# CircuitDiagramSheet.net
KiCad netlist of a schematic drawn in EasyEDA
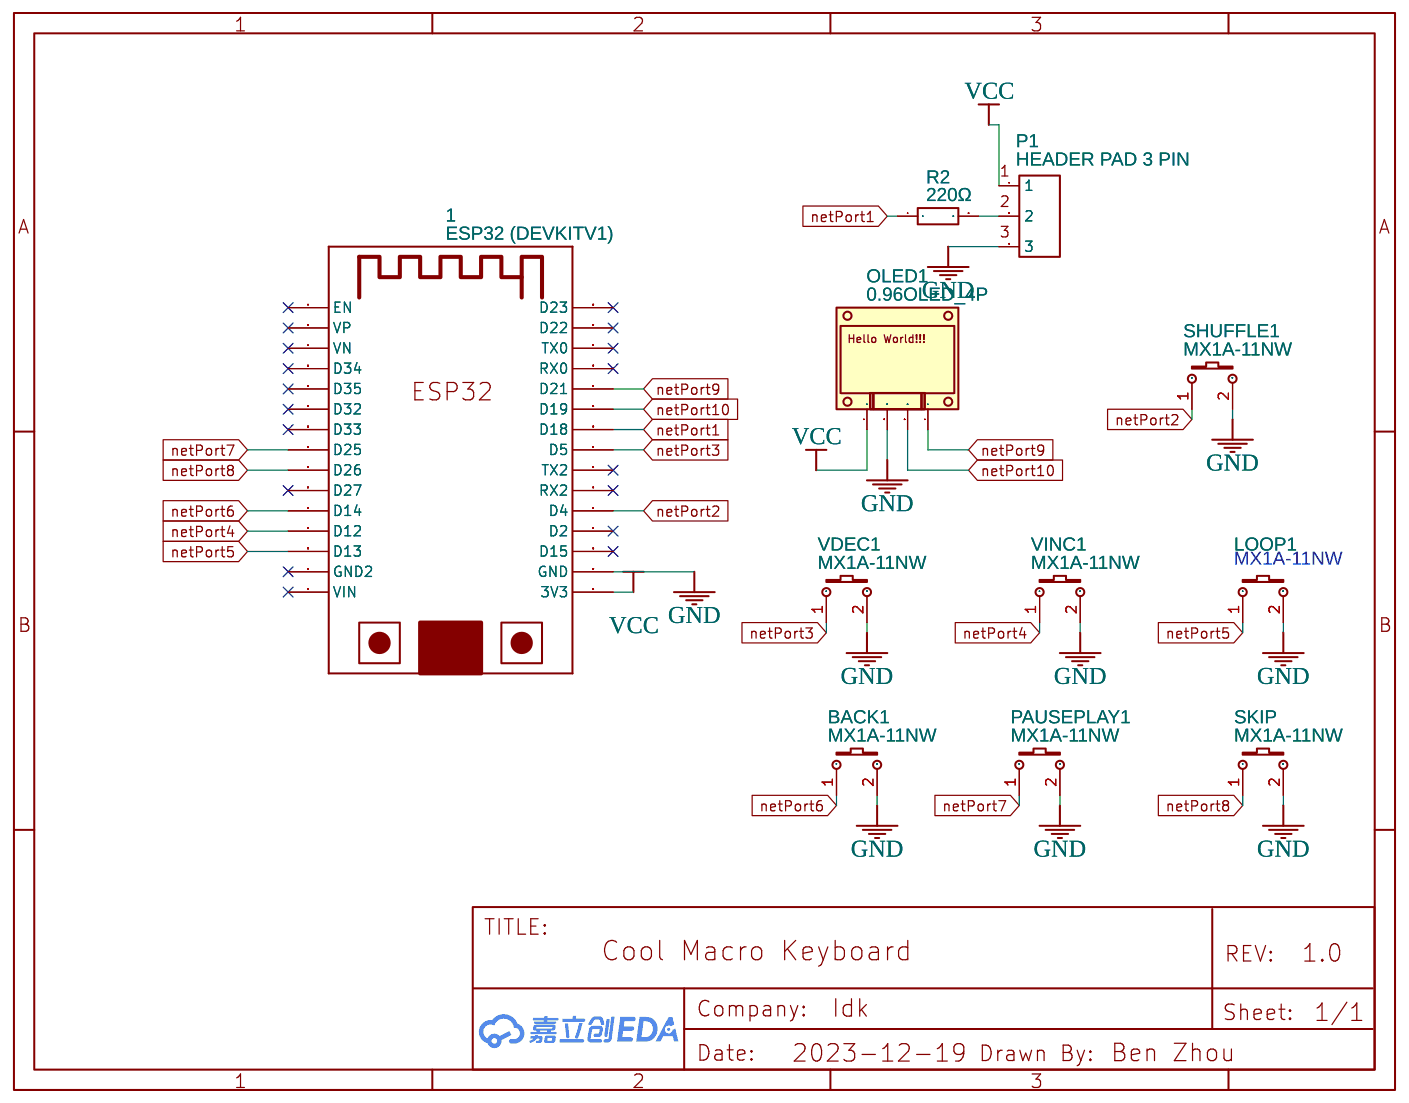
[diagram p0: schematic sheet]

(export (version "E")
  (design (tool "Eeschema 10.0.6"))
  (components
    (comp (ref "1") (value "ESP32 (DEVKITV1)") (libsource (lib "") (part "ESP32-DEVKIT-V1-30PIN")))
    (comp (ref "BACK1")
      (value "MX1A-11NW")
      (fields (field (name "Manufacturer") "CHERRY"))
      (libsource (lib "") (part "MX1A-11NW_6"))
    )
    (comp (ref "LOOP1")
      (value "SW4")
      (fields (field (name "Manufacturer") "CHERRY"))
      (libsource (lib "") (part "MX1A-11NW_4"))
    )
    (comp (ref "OLED1") (value "0.96OLED_4P") (libsource (lib "") (part "0.96OLED_4P")))
    (comp (ref "P1")
      (value "HEADER PAD 3 PIN")
      (fields (field (name "Manufacturer") "BOOMELE"))
      (libsource (lib "") (part "HEADER PAD 3 PIN"))
    )
    (comp (ref "PAUSEPLAY1")
      (value "MX1A-11NW")
      (fields (field (name "Manufacturer") "CHERRY"))
      (libsource (lib "") (part "MX1A-11NW_3"))
    )
    (comp (ref "R2")
      (value "220Ω")
      (fields (field (name "Manufacturer Part") "RSS02J2200A520NH") (field (name "Manufacturer") "台湾双羽"))
      (libsource (lib "") (part "RSS02J2200A520NH"))
    )
    (comp (ref "SHUFFLE1")
      (value "MX1A-11NW")
      (fields (field (name "Manufacturer") "CHERRY"))
      (libsource (lib "") (part "MX1A-11NW_2"))
    )
    (comp (ref "SKIP")
      (value "MX1A-11NW")
      (fields (field (name "Manufacturer") "CHERRY"))
      (libsource (lib "") (part "MX1A-11NW_1"))
    )
    (comp (ref "VDEC1")
      (value "MX1A-11NW")
      (fields (field (name "Manufacturer") "CHERRY"))
      (libsource (lib "") (part "MX1A-11NW_5"))
    )
    (comp (ref "VINC1")
      (value "MX1A-11NW")
      (fields (field (name "Manufacturer") "CHERRY"))
      (libsource (lib "") (part "MX1A-11NW"))
    )
  )
  (nets
    (net (code "1") (name "GND") (class "Default")
      (node (ref "1") (pin "GND") (pinfunction "GND_GND") (pintype "unspecified"))
      (node (ref "BACK1") (pin "2") (pinfunction "2_2") (pintype "unspecified"))
      (node (ref "LOOP1") (pin "2") (pinfunction "2_2") (pintype "unspecified"))
      (node (ref "OLED1") (pin "2") (pinfunction "2_2") (pintype "unspecified"))
      (node (ref "P1") (pin "3") (pinfunction "3_3") (pintype "input"))
      (node (ref "PAUSEPLAY1") (pin "2") (pinfunction "2_2") (pintype "unspecified"))
      (node (ref "SHUFFLE1") (pin "2") (pinfunction "2_2") (pintype "unspecified"))
      (node (ref "SKIP") (pin "2") (pinfunction "2_2") (pintype "unspecified"))
      (node (ref "VDEC1") (pin "2") (pinfunction "2_2") (pintype "unspecified"))
      (node (ref "VINC1") (pin "2") (pinfunction "2_2") (pintype "unspecified"))
    )
    (net (code "2") (name "Net-(P1-Pad2)") (class "Default")
      (node (ref "P1") (pin "2") (pinfunction "2_2") (pintype "input"))
      (node (ref "R2") (pin "2") (pinfunction "2_2") (pintype "unspecified"))
    )
    (net (code "3") (name "VCC") (class "Default")
      (node (ref "1") (pin "3V3") (pinfunction "3V3_3V3") (pintype "unspecified"))
      (node (ref "OLED1") (pin "1") (pinfunction "1_1") (pintype "unspecified"))
      (node (ref "P1") (pin "1") (pinfunction "1_1") (pintype "input"))
    )
    (net (code "4") (name "netPort1") (class "Default")
      (node (ref "1") (pin "D18") (pinfunction "D18_D18") (pintype "unspecified"))
      (node (ref "R2") (pin "1") (pinfunction "1_1") (pintype "unspecified"))
    )
    (net (code "5") (name "netPort2") (class "Default")
      (node (ref "1") (pin "D4") (pinfunction "D4_D4") (pintype "unspecified"))
      (node (ref "SHUFFLE1") (pin "1") (pinfunction "1_1") (pintype "unspecified"))
    )
    (net (code "6") (name "netPort3") (class "Default")
      (node (ref "1") (pin "D5") (pinfunction "D5_D5") (pintype "unspecified"))
      (node (ref "VDEC1") (pin "1") (pinfunction "1_1") (pintype "unspecified"))
    )
    (net (code "7") (name "netPort4") (class "Default")
      (node (ref "1") (pin "D12") (pinfunction "D12_D12") (pintype "unspecified"))
      (node (ref "VINC1") (pin "1") (pinfunction "1_1") (pintype "unspecified"))
    )
    (net (code "8") (name "netPort5") (class "Default")
      (node (ref "1") (pin "D13") (pinfunction "D13_D13") (pintype "unspecified"))
      (node (ref "LOOP1") (pin "1") (pinfunction "1_1") (pintype "unspecified"))
    )
    (net (code "9") (name "netPort6") (class "Default")
      (node (ref "1") (pin "D14") (pinfunction "D14_D14") (pintype "unspecified"))
      (node (ref "BACK1") (pin "1") (pinfunction "1_1") (pintype "unspecified"))
    )
    (net (code "10") (name "netPort7") (class "Default")
      (node (ref "1") (pin "D25") (pinfunction "D25_D25") (pintype "unspecified"))
      (node (ref "PAUSEPLAY1") (pin "1") (pinfunction "1_1") (pintype "unspecified"))
    )
    (net (code "11") (name "netPort8") (class "Default")
      (node (ref "1") (pin "D26") (pinfunction "D26_D26") (pintype "unspecified"))
      (node (ref "SKIP") (pin "1") (pinfunction "1_1") (pintype "unspecified"))
    )
    (net (code "12") (name "netPort9") (class "Default")
      (node (ref "1") (pin "D21") (pinfunction "D21_D21") (pintype "unspecified"))
      (node (ref "OLED1") (pin "4") (pinfunction "4_4") (pintype "unspecified"))
    )
    (net (code "13") (name "netPort10") (class "Default")
      (node (ref "1") (pin "D19") (pinfunction "D19_D19") (pintype "unspecified"))
      (node (ref "OLED1") (pin "3") (pinfunction "3_3") (pintype "unspecified"))
    )
    (net (code "14") (name "unconnected-(1-PadD2)") (class "Default")
      (node (ref "1") (pin "D2") (pinfunction "D2_D2") (pintype "unspecified+no_connect"))
    )
    (net (code "15") (name "unconnected-(1-PadD15)") (class "Default")
      (node (ref "1") (pin "D15") (pinfunction "D15_D15") (pintype "unspecified+no_connect"))
    )
    (net (code "16") (name "unconnected-(1-PadD22)") (class "Default")
      (node (ref "1") (pin "D22") (pinfunction "D22_D22") (pintype "unspecified+no_connect"))
    )
    (net (code "17") (name "unconnected-(1-PadD23)") (class "Default")
      (node (ref "1") (pin "D23") (pinfunction "D23_D23") (pintype "unspecified+no_connect"))
    )
    (net (code "18") (name "unconnected-(1-PadD27)") (class "Default")
      (node (ref "1") (pin "D27") (pinfunction "D27_D27") (pintype "unspecified+no_connect"))
    )
    (net (code "19") (name "unconnected-(1-PadD32)") (class "Default")
      (node (ref "1") (pin "D32") (pinfunction "D32_D32") (pintype "unspecified+no_connect"))
    )
    (net (code "20") (name "unconnected-(1-PadD33)") (class "Default")
      (node (ref "1") (pin "D33") (pinfunction "D33_D33") (pintype "unspecified+no_connect"))
    )
    (net (code "21") (name "unconnected-(1-PadD34)") (class "Default")
      (node (ref "1") (pin "D34") (pinfunction "D34_D34") (pintype "unspecified+no_connect"))
    )
    (net (code "22") (name "unconnected-(1-PadD35)") (class "Default")
      (node (ref "1") (pin "D35") (pinfunction "D35_D35") (pintype "unspecified+no_connect"))
    )
    (net (code "23") (name "unconnected-(1-PadEN)") (class "Default")
      (node (ref "1") (pin "EN") (pinfunction "EN_EN") (pintype "unspecified+no_connect"))
    )
    (net (code "24") (name "unconnected-(1-PadGND2)") (class "Default")
      (node (ref "1") (pin "GND2") (pinfunction "GND2_GND2") (pintype "unspecified+no_connect"))
    )
    (net (code "25") (name "unconnected-(1-PadRX0)") (class "Default")
      (node (ref "1") (pin "RX0") (pinfunction "RX0_RX0") (pintype "unspecified+no_connect"))
    )
    (net (code "26") (name "unconnected-(1-PadRX2)") (class "Default")
      (node (ref "1") (pin "RX2") (pinfunction "RX2_RX2") (pintype "unspecified+no_connect"))
    )
    (net (code "27") (name "unconnected-(1-PadTX0)") (class "Default")
      (node (ref "1") (pin "TX0") (pinfunction "TX0_TX0") (pintype "unspecified+no_connect"))
    )
    (net (code "28") (name "unconnected-(1-PadTX2)") (class "Default")
      (node (ref "1") (pin "TX2") (pinfunction "TX2_TX2") (pintype "unspecified+no_connect"))
    )
    (net (code "29") (name "unconnected-(1-PadVIN)") (class "Default")
      (node (ref "1") (pin "VIN") (pinfunction "VIN_VIN") (pintype "unspecified+no_connect"))
    )
    (net (code "30") (name "unconnected-(1-PadVN)") (class "Default")
      (node (ref "1") (pin "VN") (pinfunction "VN_VN") (pintype "unspecified+no_connect"))
    )
    (net (code "31") (name "unconnected-(1-PadVP)") (class "Default")
      (node (ref "1") (pin "VP") (pinfunction "VP_VP") (pintype "unspecified+no_connect"))
    )
  )
)
